# adc_power.net
KiCad netlist of a schematic drawn in Altium Designer
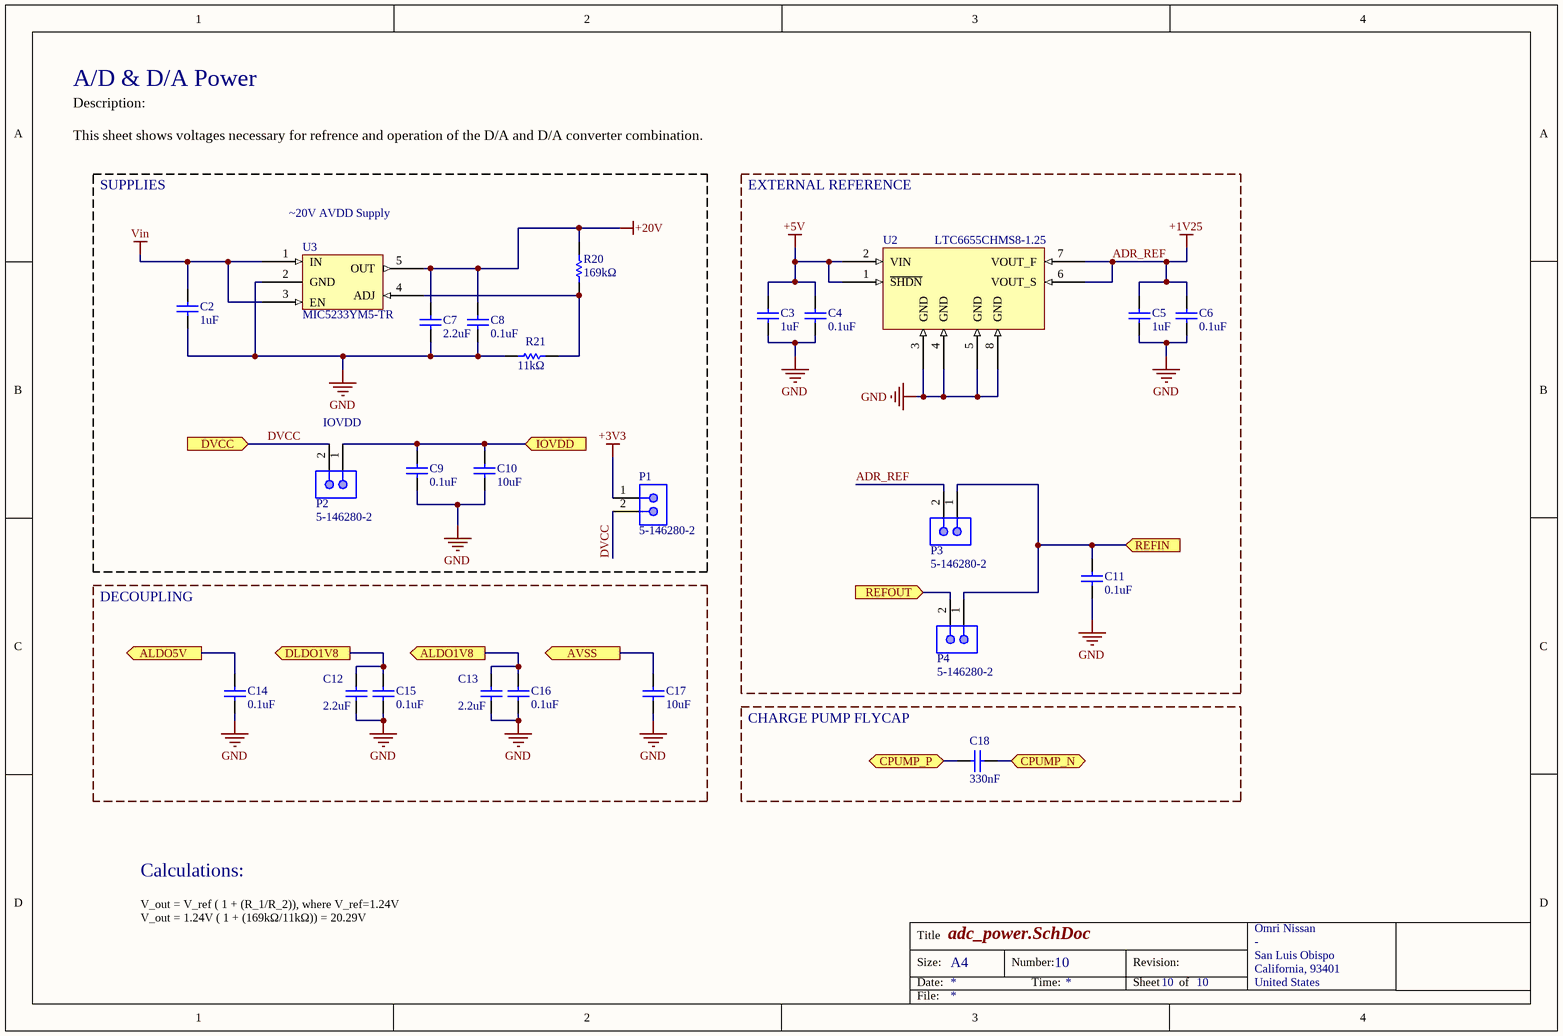
[diagram p0: adc_power.SchDoc]

(export (version "E")
  (design (tool "Eeschema 10.0.6"))
  (components
    (comp (ref "C2")
      (value "1uF")
      (footprint "CAPC1608X90X20LL10")
      (fields
        (field (name "MANUFACTURER") "TDK")
        (field (name "PCN PART NUMBER") "MLCCPartNumberChange30/Nov/2012")
        (field (name "TOLERANCE") "±10%")
      )
      (libsource (lib "Altium Content Vault") (part "CAP-NP-2"))
    )
    (comp (ref "C3")
      (value "1uF")
      (footprint "CAPC1608X90X20LL10")
      (fields
        (field (name "MANUFACTURER") "TDK")
        (field (name "PCN PART NUMBER") "MLCCPartNumberChange30/Nov/2012")
        (field (name "TOLERANCE") "±10%")
      )
      (libsource (lib "Altium Content Vault") (part "CAP-NP-2"))
    )
    (comp (ref "C4")
      (value "0.1uF")
      (footprint "CAPC1608X90X35ML10T15")
      (fields
        (field (name "TOLERANCE") "10%")
        (field (name "VOLTAGE") "50V")
        (field (name "MANUFACTURER") "Murata")
      )
      (libsource (lib "Altium Content Vault") (part "CAP-NP-2"))
    )
    (comp (ref "C5")
      (value "1uF")
      (footprint "CAPC1608X90X20LL10")
      (fields
        (field (name "MANUFACTURER") "TDK")
        (field (name "PCN PART NUMBER") "MLCCPartNumberChange30/Nov/2012")
        (field (name "TOLERANCE") "±10%")
      )
      (libsource (lib "Altium Content Vault") (part "CAP-NP-2"))
    )
    (comp (ref "C6")
      (value "0.1uF")
      (footprint "CAPC1608X90X35ML10T15")
      (fields
        (field (name "TOLERANCE") "10%")
        (field (name "VOLTAGE") "50V")
        (field (name "MANUFACTURER") "Murata")
      )
      (libsource (lib "Altium Content Vault") (part "CAP-NP-2"))
    )
    (comp (ref "C7")
      (value "2.2uF")
      (footprint "CAPC2013X145X20LL20")
      (fields
        (field (name "MANUFACTURER") "TDK")
        (field (name "TOLERANCE") "±10%")
        (field (name "PCN PART NUMBER") "MLCCPartNumberChange30/Nov/2012")
      )
      (libsource (lib "Altium Content Vault") (part "CAP-NP-2"))
    )
    (comp (ref "C8")
      (value "0.1uF")
      (footprint "CAPC1608X90X35ML10T15")
      (fields
        (field (name "TOLERANCE") "10%")
        (field (name "VOLTAGE") "50V")
        (field (name "MANUFACTURER") "Murata")
      )
      (libsource (lib "Altium Content Vault") (part "CAP-NP-2"))
    )
    (comp (ref "C9")
      (value "0.1uF")
      (footprint "CAPC1608X90X35ML10T15")
      (fields
        (field (name "TOLERANCE") "10%")
        (field (name "VOLTAGE") "50V")
        (field (name "MANUFACTURER") "Murata")
      )
      (libsource (lib "Altium Content Vault") (part "CAP-NP-2"))
    )
    (comp (ref "C10")
      (value "10uF")
      (footprint "CAPC3216X180X20LL20")
      (fields
        (field (name "MANUFACTURER") "TDK")
        (field (name "PCN PART NUMBER") "MLCCPartNumberChange30/Nov/2012")
        (field (name "TOLERANCE") "±10%")
      )
      (libsource (lib "Altium Content Vault") (part "CAP-NP-2"))
    )
    (comp (ref "C11")
      (value "0.1uF")
      (footprint "CAPC1608X90X35ML10T15")
      (fields
        (field (name "TOLERANCE") "10%")
        (field (name "VOLTAGE") "50V")
        (field (name "MANUFACTURER") "Murata")
      )
      (libsource (lib "Altium Content Vault") (part "CAP-NP-2"))
    )
    (comp (ref "C12")
      (value "2.2uF")
      (footprint "CAPC2013X145X20LL20")
      (fields
        (field (name "MANUFACTURER") "TDK")
        (field (name "TOLERANCE") "±10%")
        (field (name "PCN PART NUMBER") "MLCCPartNumberChange30/Nov/2012")
      )
      (libsource (lib "Altium Content Vault") (part "CAP-NP-2"))
    )
    (comp (ref "C13")
      (value "2.2uF")
      (footprint "CAPC2013X145X20LL20")
      (fields
        (field (name "MANUFACTURER") "TDK")
        (field (name "TOLERANCE") "±10%")
        (field (name "PCN PART NUMBER") "MLCCPartNumberChange30/Nov/2012")
      )
      (libsource (lib "Altium Content Vault") (part "CAP-NP-2"))
    )
    (comp (ref "C14")
      (value "0.1uF")
      (footprint "CAPC1608X90X35ML10T15")
      (fields
        (field (name "TOLERANCE") "10%")
        (field (name "VOLTAGE") "50V")
        (field (name "MANUFACTURER") "Murata")
      )
      (libsource (lib "Altium Content Vault") (part "CAP-NP-2"))
    )
    (comp (ref "C15")
      (value "0.1uF")
      (footprint "CAPC1608X90X35ML10T15")
      (fields
        (field (name "TOLERANCE") "10%")
        (field (name "VOLTAGE") "50V")
        (field (name "MANUFACTURER") "Murata")
      )
      (libsource (lib "Altium Content Vault") (part "CAP-NP-2"))
    )
    (comp (ref "C16")
      (value "0.1uF")
      (footprint "CAPC1608X90X35ML10T15")
      (fields
        (field (name "TOLERANCE") "10%")
        (field (name "VOLTAGE") "50V")
        (field (name "MANUFACTURER") "Murata")
      )
      (libsource (lib "Altium Content Vault") (part "CAP-NP-2"))
    )
    (comp (ref "C17")
      (value "10uF")
      (footprint "CAPC3216X180X20LL20")
      (fields
        (field (name "MANUFACTURER") "TDK")
        (field (name "PCN PART NUMBER") "MLCCPartNumberChange30/Nov/2012")
        (field (name "TOLERANCE") "±10%")
      )
      (libsource (lib "Altium Content Vault") (part "CAP-NP-2"))
    )
    (comp (ref "C18")
      (value "330nF")
      (footprint "CAPC1608X90X35NL10T15")
      (description "GRM188R71A334KA61D")
      (fields (field (name "MANUFACTURER") "Murata"))
      (libsource (lib "Altium Content Vault") (part "CAP"))
    )
    (comp (ref "P1")
      (value "5-146280-2")
      (footprint "TECO-5-146280-2_V")
      (fields (field (name "MANUFACTURER") "TE Connectivity"))
      (libsource (lib "Altium Content Vault") (part "CN-1P-M-R2"))
    )
    (comp (ref "P2")
      (value "5-146280-2")
      (footprint "TECO-5-146280-2_V")
      (fields (field (name "MANUFACTURER") "TE Connectivity"))
      (libsource (lib "") (part "CN-1P-M-R2_1"))
    )
    (comp (ref "P3")
      (value "5-146280-2")
      (footprint "TECO-5-146280-2_V")
      (fields (field (name "MANUFACTURER") "TE Connectivity"))
      (libsource (lib "") (part "CN-1P-M-R2_1"))
    )
    (comp (ref "P4")
      (value "5-146280-2")
      (footprint "TECO-5-146280-2_V")
      (fields (field (name "MANUFACTURER") "TE Connectivity"))
      (libsource (lib "") (part "CN-1P-M-R2_1"))
    )
    (comp (ref "R20")
      (value "169kΩ")
      (footprint "RESC1608X55X30ML15T15")
      (description "ERJ-3EKF1693V")
      (fields (field (name "MANUFACTURER") "Panasonic"))
      (libsource (lib "Altium Content Vault") (part "RES"))
    )
    (comp (ref "R21")
      (value "11kΩ")
      (footprint "RESC1609X50X30ML10T20")
      (description "CRCW060311K0FKEA")
      (fields (field (name "MANUFACTURER") "Vishay Dale"))
      (libsource (lib "Altium Content Vault") (part "RES"))
    )
    (comp (ref "U2")
      (value "LTC6655CHMS8-1.25")
      (footprint "ADI-RM-8_L")
      (description "IC VREF SERIES 1.25V 8MSOP")
      (fields (field (name "TOLERANCE") "0.05%"))
      (libsource (lib "digital_power") (part "LTC6655CHMS8-1.25#PBF"))
    )
    (comp (ref "U3")
      (value "MIC5233YM5-TR")
      (footprint "MF05A_L")
      (description "IC REG LDO ADJ .1A SOT23-5")
      (libsource (lib "digital_power") (part "MIC5233YM5-TR_1"))
    )
  )
  (nets
    (net (code "1") (name "+1V25") (class "Default")
      (node (ref "C5") (pin "1") (pinfunction "1_1") (pintype "passive"))
      (node (ref "C6") (pin "2") (pinfunction "2_2") (pintype "passive"))
      (node (ref "P3") (pin "2") (pinfunction "2_2") (pintype "passive"))
      (node (ref "U2") (pin "6") (pinfunction "VOUT_S_6") (pintype "input"))
      (node (ref "U2") (pin "7") (pinfunction "VOUT_F_7") (pintype "input"))
    )
    (net (code "2") (name "+3V3") (class "Default")
      (node (ref "P1") (pin "1") (pinfunction "1_1") (pintype "passive"))
    )
    (net (code "3") (name "+5V") (class "Default")
      (node (ref "C3") (pin "1") (pinfunction "1_1") (pintype "passive"))
      (node (ref "C4") (pin "2") (pinfunction "2_2") (pintype "passive"))
      (node (ref "U2") (pin "1") (pinfunction "SHDN_1") (pintype "input"))
      (node (ref "U2") (pin "2") (pinfunction "VIN_2") (pintype "input"))
    )
    (net (code "4") (name "+20V") (class "Default")
      (node (ref "C7") (pin "2") (pinfunction "2_2") (pintype "passive"))
      (node (ref "C8") (pin "2") (pinfunction "2_2") (pintype "passive"))
      (node (ref "R20") (pin "2") (pinfunction "2_2") (pintype "passive"))
      (node (ref "U3") (pin "5") (pinfunction "OUT_5") (pintype "output"))
    )
    (net (code "5") (name "/ALDO1V8") (class "Default")
      (node (ref "C13") (pin "2") (pinfunction "2_2") (pintype "passive"))
      (node (ref "C16") (pin "2") (pinfunction "2_2") (pintype "passive"))
    )
    (net (code "6") (name "/ALDO5V") (class "Default")
      (node (ref "C14") (pin "2") (pinfunction "2_2") (pintype "passive"))
    )
    (net (code "7") (name "/AVSS") (class "Default")
      (node (ref "C17") (pin "2") (pinfunction "2_2") (pintype "passive"))
    )
    (net (code "8") (name "/CPUMP_N") (class "Default")
      (node (ref "C18") (pin "2") (pinfunction "2_2") (pintype "passive"))
    )
    (net (code "9") (name "/CPUMP_P") (class "Default")
      (node (ref "C18") (pin "1") (pinfunction "1_1") (pintype "passive"))
    )
    (net (code "10") (name "/DLDO1V8") (class "Default")
      (node (ref "C12") (pin "2") (pinfunction "2_2") (pintype "passive"))
      (node (ref "C15") (pin "2") (pinfunction "2_2") (pintype "passive"))
    )
    (net (code "11") (name "/DVCC") (class "Default")
      (node (ref "P1") (pin "2") (pinfunction "2_2") (pintype "passive"))
      (node (ref "P2") (pin "2") (pinfunction "2_2") (pintype "passive"))
    )
    (net (code "12") (name "/IOVDD") (class "Default")
      (node (ref "C10") (pin "2") (pinfunction "2_2") (pintype "passive"))
      (node (ref "C9") (pin "2") (pinfunction "2_2") (pintype "passive"))
      (node (ref "P2") (pin "1") (pinfunction "1_1") (pintype "passive"))
    )
    (net (code "13") (name "/REFIN") (class "Default")
      (node (ref "C11") (pin "2") (pinfunction "2_2") (pintype "passive"))
      (node (ref "P3") (pin "1") (pinfunction "1_1") (pintype "passive"))
      (node (ref "P4") (pin "1") (pinfunction "1_1") (pintype "passive"))
    )
    (net (code "14") (name "/REFOUT") (class "Default")
      (node (ref "P4") (pin "2") (pinfunction "2_2") (pintype "passive"))
    )
    (net (code "15") (name "GND") (class "Default")
      (node (ref "C10") (pin "1") (pinfunction "1_1") (pintype "passive"))
      (node (ref "C11") (pin "1") (pinfunction "1_1") (pintype "passive"))
      (node (ref "C12") (pin "1") (pinfunction "1_1") (pintype "passive"))
      (node (ref "C13") (pin "1") (pinfunction "1_1") (pintype "passive"))
      (node (ref "C14") (pin "1") (pinfunction "1_1") (pintype "passive"))
      (node (ref "C15") (pin "1") (pinfunction "1_1") (pintype "passive"))
      (node (ref "C16") (pin "1") (pinfunction "1_1") (pintype "passive"))
      (node (ref "C17") (pin "1") (pinfunction "1_1") (pintype "passive"))
      (node (ref "C2") (pin "2") (pinfunction "2_2") (pintype "passive"))
      (node (ref "C3") (pin "2") (pinfunction "2_2") (pintype "passive"))
      (node (ref "C4") (pin "1") (pinfunction "1_1") (pintype "passive"))
      (node (ref "C5") (pin "2") (pinfunction "2_2") (pintype "passive"))
      (node (ref "C6") (pin "1") (pinfunction "1_1") (pintype "passive"))
      (node (ref "C7") (pin "1") (pinfunction "1_1") (pintype "passive"))
      (node (ref "C8") (pin "1") (pinfunction "1_1") (pintype "passive"))
      (node (ref "C9") (pin "1") (pinfunction "1_1") (pintype "passive"))
      (node (ref "R21") (pin "1") (pinfunction "1_1") (pintype "passive"))
      (node (ref "U2") (pin "3") (pinfunction "GND_3") (pintype "input"))
      (node (ref "U2") (pin "4") (pinfunction "GND_4") (pintype "input"))
      (node (ref "U2") (pin "5") (pinfunction "GND_5") (pintype "input"))
      (node (ref "U2") (pin "8") (pinfunction "GND_8") (pintype "input"))
      (node (ref "U3") (pin "2") (pinfunction "GND_2") (pintype "power_in"))
    )
    (net (code "16") (name "Net-(U3-ADJ)") (class "Default")
      (node (ref "R20") (pin "1") (pinfunction "1_1") (pintype "passive"))
      (node (ref "R21") (pin "2") (pinfunction "2_2") (pintype "passive"))
      (node (ref "U3") (pin "4") (pinfunction "ADJ_4") (pintype "input"))
    )
    (net (code "17") (name "Vin") (class "Default")
      (node (ref "C2") (pin "1") (pinfunction "1_1") (pintype "passive"))
      (node (ref "U3") (pin "1") (pinfunction "IN_1") (pintype "input"))
      (node (ref "U3") (pin "3") (pinfunction "EN_3") (pintype "input"))
    )
  )
)
